# Gear_Shifters.net
KiCad netlist of a schematic drawn in EAGLE
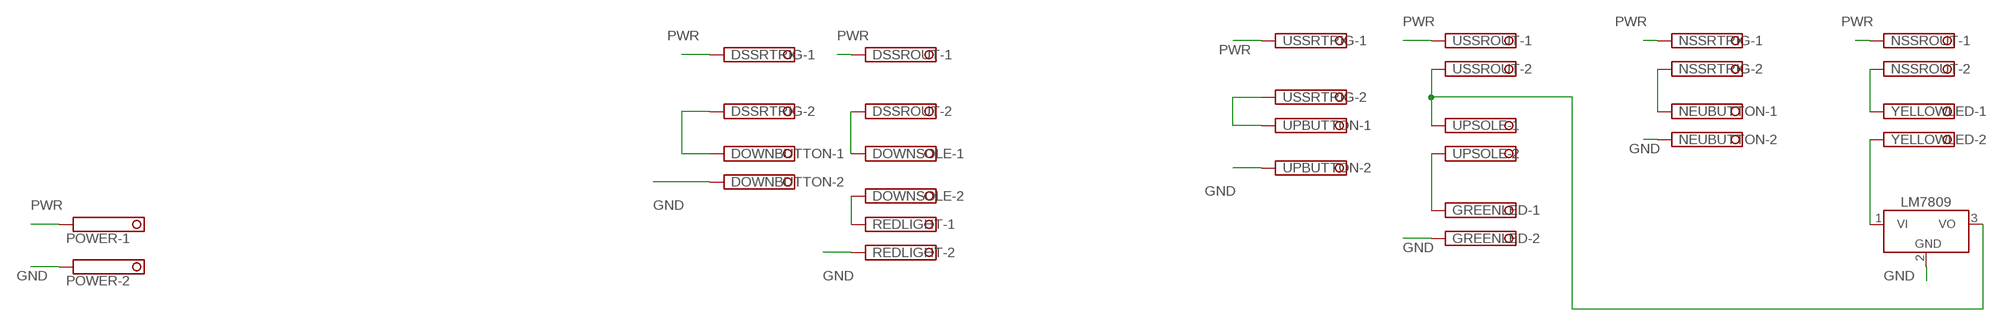
[diagram p0: schematic, sheet 1]

(export (version "E")
  (design (tool "Eeschema 10.0.6"))
  (components
    (comp (ref "DOWNBUTTON")
      (value "TERMINAL-BLOCK-3.5MM-2-PIN-ROUND-PAD")
      (footprint "eagle-import:TERMINAL-BLOCK-2-PIN-3.5MM-ROUND-PAD")
      (libsource (lib "eagle-import") (part "TERMINAL-BLOCK-3.5MM-2-PIN-ROUND-PAD"))
    )
    (comp (ref "DOWNSOLE")
      (value "TERMINAL-BLOCK-3.5MM-2-PIN-ROUND-PAD")
      (footprint "eagle-import:TERMINAL-BLOCK-2-PIN-3.5MM-ROUND-PAD")
      (libsource (lib "eagle-import") (part "TERMINAL-BLOCK-3.5MM-2-PIN-ROUND-PAD"))
    )
    (comp (ref "DSSROUT")
      (value "TERMINAL-BLOCK-3.5MM-2-PIN-ROUND-PAD")
      (footprint "eagle-import:TERMINAL-BLOCK-2-PIN-3.5MM-ROUND-PAD")
      (libsource (lib "eagle-import") (part "TERMINAL-BLOCK-3.5MM-2-PIN-ROUND-PAD"))
    )
    (comp (ref "DSSRTRIG")
      (value "TERMINAL-BLOCK-3.5MM-2-PIN-ROUND-PAD")
      (footprint "eagle-import:TERMINAL-BLOCK-2-PIN-3.5MM-ROUND-PAD")
      (libsource (lib "eagle-import") (part "TERMINAL-BLOCK-3.5MM-2-PIN-ROUND-PAD"))
    )
    (comp (ref "GREENLED")
      (value "TERMINAL-BLOCK-3.5MM-2-PIN-ROUND-PAD")
      (footprint "eagle-import:TERMINAL-BLOCK-2-PIN-3.5MM-ROUND-PAD")
      (libsource (lib "eagle-import") (part "TERMINAL-BLOCK-3.5MM-2-PIN-ROUND-PAD"))
    )
    (comp (ref "LM7809")
      (value "LM7805_TO220V")
      (footprint "eagle-import:TO220V")
      (fields (field (name "MANUFACTURER") "Generic"))
      (libsource (lib "eagle-import") (part "LM7805_TO220V"))
    )
    (comp (ref "NEUBUTTON")
      (value "TERMINAL-BLOCK-3.5MM-2-PIN-ROUND-PAD")
      (footprint "eagle-import:TERMINAL-BLOCK-2-PIN-3.5MM-ROUND-PAD")
      (libsource (lib "eagle-import") (part "TERMINAL-BLOCK-3.5MM-2-PIN-ROUND-PAD"))
    )
    (comp (ref "NSSROUT")
      (value "TERMINAL-BLOCK-3.5MM-2-PIN-ROUND-PAD")
      (footprint "eagle-import:TERMINAL-BLOCK-2-PIN-3.5MM-ROUND-PAD")
      (libsource (lib "eagle-import") (part "TERMINAL-BLOCK-3.5MM-2-PIN-ROUND-PAD"))
    )
    (comp (ref "NSSRTRIG")
      (value "TERMINAL-BLOCK-3.5MM-2-PIN-ROUND-PAD")
      (footprint "eagle-import:TERMINAL-BLOCK-2-PIN-3.5MM-ROUND-PAD")
      (libsource (lib "eagle-import") (part "TERMINAL-BLOCK-3.5MM-2-PIN-ROUND-PAD"))
    )
    (comp (ref "POWER")
      (value "TERMINAL-BLOCK-3.5MM-2-PIN-ROUND-PAD")
      (footprint "eagle-import:TERMINAL-BLOCK-2-PIN-3.5MM-ROUND-PAD")
      (libsource (lib "eagle-import") (part "TERMINAL-BLOCK-3.5MM-2-PIN-ROUND-PAD"))
    )
    (comp (ref "REDLIGHT")
      (value "TERMINAL-BLOCK-3.5MM-2-PIN-ROUND-PAD")
      (footprint "eagle-import:TERMINAL-BLOCK-2-PIN-3.5MM-ROUND-PAD")
      (libsource (lib "eagle-import") (part "TERMINAL-BLOCK-3.5MM-2-PIN-ROUND-PAD"))
    )
    (comp (ref "UPBUTTON")
      (value "TERMINAL-BLOCK-3.5MM-2-PIN-ROUND-PAD")
      (footprint "eagle-import:TERMINAL-BLOCK-2-PIN-3.5MM-ROUND-PAD")
      (libsource (lib "eagle-import") (part "TERMINAL-BLOCK-3.5MM-2-PIN-ROUND-PAD"))
    )
    (comp (ref "UPSOLE")
      (value "TERMINAL-BLOCK-3.5MM-2-PIN-ROUND-PAD")
      (footprint "eagle-import:TERMINAL-BLOCK-2-PIN-3.5MM-ROUND-PAD")
      (libsource (lib "eagle-import") (part "TERMINAL-BLOCK-3.5MM-2-PIN-ROUND-PAD"))
    )
    (comp (ref "USSROUT")
      (value "TERMINAL-BLOCK-3.5MM-2-PIN-ROUND-PAD")
      (footprint "eagle-import:TERMINAL-BLOCK-2-PIN-3.5MM-ROUND-PAD")
      (libsource (lib "eagle-import") (part "TERMINAL-BLOCK-3.5MM-2-PIN-ROUND-PAD"))
    )
    (comp (ref "USSRTRIG")
      (value "TERMINAL-BLOCK-3.5MM-2-PIN-ROUND-PAD")
      (footprint "eagle-import:TERMINAL-BLOCK-2-PIN-3.5MM-ROUND-PAD")
      (libsource (lib "eagle-import") (part "TERMINAL-BLOCK-3.5MM-2-PIN-ROUND-PAD"))
    )
    (comp (ref "YELLOWLED")
      (value "TERMINAL-BLOCK-3.5MM-2-PIN-ROUND-PAD")
      (footprint "eagle-import:TERMINAL-BLOCK-2-PIN-3.5MM-ROUND-PAD")
      (libsource (lib "eagle-import") (part "TERMINAL-BLOCK-3.5MM-2-PIN-ROUND-PAD"))
    )
  )
  (nets
    (net (code "1") (name "/GND") (class "Default")
      (node (ref "DOWNBUTTON") (pin "2") (pinfunction "K_2") (pintype "passive"))
      (node (ref "GREENLED") (pin "2") (pinfunction "K_2") (pintype "passive"))
      (node (ref "LM7809") (pin "2") (pinfunction "GND_2") (pintype "passive"))
      (node (ref "NEUBUTTON") (pin "2") (pinfunction "K_2") (pintype "passive"))
      (node (ref "POWER") (pin "2") (pinfunction "K_2") (pintype "passive"))
      (node (ref "REDLIGHT") (pin "2") (pinfunction "K_2") (pintype "passive"))
      (node (ref "UPBUTTON") (pin "2") (pinfunction "K_2") (pintype "passive"))
    )
    (net (code "2") (name "/PWR") (class "Default")
      (node (ref "DSSROUT") (pin "1") (pinfunction "K_1") (pintype "passive"))
      (node (ref "DSSRTRIG") (pin "1") (pinfunction "K_1") (pintype "passive"))
      (node (ref "NSSROUT") (pin "1") (pinfunction "K_1") (pintype "passive"))
      (node (ref "NSSRTRIG") (pin "1") (pinfunction "K_1") (pintype "passive"))
      (node (ref "POWER") (pin "1") (pinfunction "K_1") (pintype "passive"))
      (node (ref "USSROUT") (pin "1") (pinfunction "K_1") (pintype "passive"))
      (node (ref "USSRTRIG") (pin "1") (pinfunction "K_1") (pintype "passive"))
    )
    (net (code "3") (name "Net-(DOWNBUTTONA-K)") (class "Default")
      (node (ref "DOWNBUTTON") (pin "1") (pinfunction "K_1") (pintype "passive"))
      (node (ref "DSSRTRIG") (pin "2") (pinfunction "K_2") (pintype "passive"))
    )
    (net (code "4") (name "Net-(DOWNSOLEA-K)") (class "Default")
      (node (ref "DOWNSOLE") (pin "1") (pinfunction "K_1") (pintype "passive"))
      (node (ref "DSSROUT") (pin "2") (pinfunction "K_2") (pintype "passive"))
    )
    (net (code "5") (name "Net-(DOWNSOLEB-K)") (class "Default")
      (node (ref "DOWNSOLE") (pin "2") (pinfunction "K_2") (pintype "passive"))
      (node (ref "REDLIGHT") (pin "1") (pinfunction "K_1") (pintype "passive"))
    )
    (net (code "6") (name "Net-(GREENLEDA-K)") (class "Default")
      (node (ref "GREENLED") (pin "1") (pinfunction "K_1") (pintype "passive"))
      (node (ref "UPSOLE") (pin "2") (pinfunction "K_2") (pintype "passive"))
    )
    (net (code "7") (name "Net-(LM7809-VI)") (class "Default")
      (node (ref "LM7809") (pin "1") (pinfunction "VI_1") (pintype "input"))
      (node (ref "YELLOWLED") (pin "2") (pinfunction "K_2") (pintype "passive"))
    )
    (net (code "8") (name "Net-(LM7809-VO)") (class "Default")
      (node (ref "LM7809") (pin "3") (pinfunction "VO_3") (pintype "output"))
      (node (ref "UPSOLE") (pin "1") (pinfunction "K_1") (pintype "passive"))
      (node (ref "USSROUT") (pin "2") (pinfunction "K_2") (pintype "passive"))
    )
    (net (code "9") (name "Net-(NEUBUTTONA-K)") (class "Default")
      (node (ref "NEUBUTTON") (pin "1") (pinfunction "K_1") (pintype "passive"))
      (node (ref "NSSRTRIG") (pin "2") (pinfunction "K_2") (pintype "passive"))
    )
    (net (code "10") (name "Net-(NSSROUTB-K)") (class "Default")
      (node (ref "NSSROUT") (pin "2") (pinfunction "K_2") (pintype "passive"))
      (node (ref "YELLOWLED") (pin "1") (pinfunction "K_1") (pintype "passive"))
    )
    (net (code "11") (name "Net-(UPBUTTONA-K)") (class "Default")
      (node (ref "UPBUTTON") (pin "1") (pinfunction "K_1") (pintype "passive"))
      (node (ref "USSRTRIG") (pin "2") (pinfunction "K_2") (pintype "passive"))
    )
  )
)
